# TDC_VTUNE_DAC.net
KiCad netlist of a schematic drawn in Altium Designer
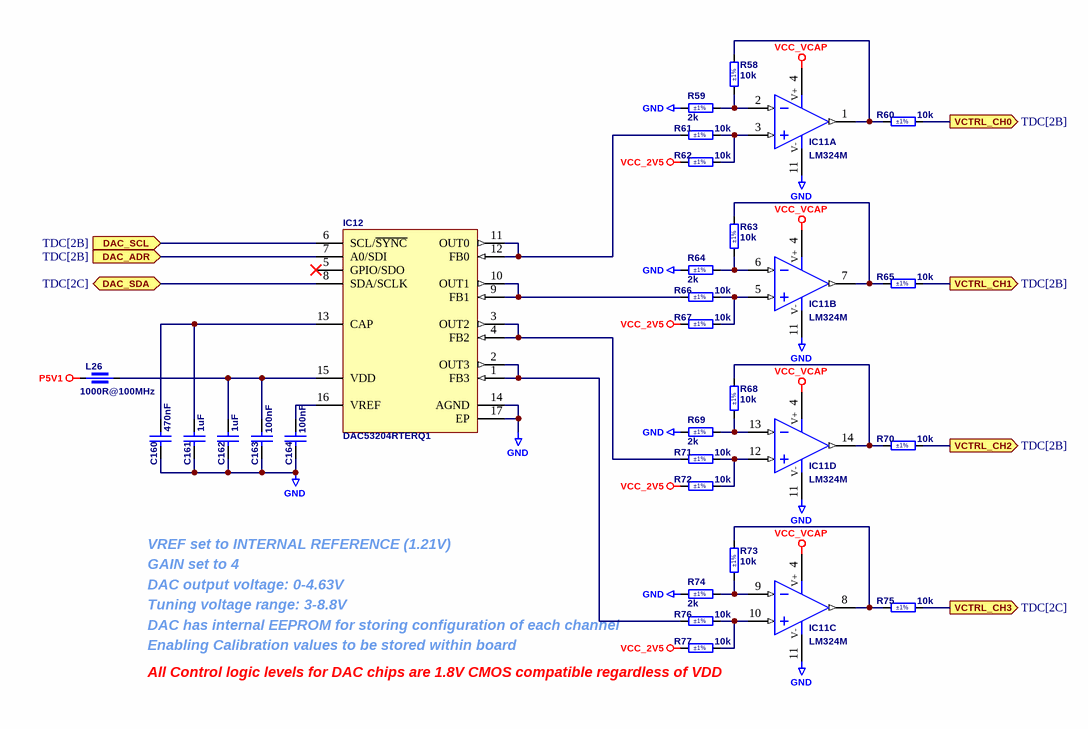
[diagram p0: TDC_VTUNE_DAC.SchDoc]

(export (version "E")
  (design (tool "Eeschema 10.0.6"))
  (components
    (comp (ref "C160")
      (value "470nF")
      (footprint "CAPC1005X55N")
      (description "Non-polarised capacitor")
      (fields
        (field (name "PART NUMBER") "CC0402_470NF_10V_10%_X7R")
        (field (name "VOLTAGE") "10V")
        (field (name "AUTHOR") "CERN DEM BC")
      )
      (libsource (lib "Capacitors") (part "Capacitor - non polarized"))
    )
    (comp (ref "C161")
      (value "1uF")
      (footprint "CAPC1005X55N")
      (description "Non-polarised capacitor")
      (fields
        (field (name "PART NUMBER") "CC0402_1UF_16V_10%_X5R")
        (field (name "VOLTAGE") "16V")
        (field (name "AUTHOR") "CERN DEM JLC")
      )
      (libsource (lib "Capacitors") (part "Capacitor - non polarized"))
    )
    (comp (ref "C162")
      (value "1uF")
      (footprint "CAPC1005X55N")
      (description "Non-polarised capacitor")
      (fields
        (field (name "PART NUMBER") "CC0402_1UF_16V_10%_X5R")
        (field (name "VOLTAGE") "16V")
        (field (name "AUTHOR") "CERN DEM JLC")
      )
      (libsource (lib "Capacitors") (part "Capacitor - non polarized"))
    )
    (comp (ref "C163")
      (value "100nF")
      (footprint "CAPC1005X55N")
      (description "Non-polarised capacitor")
      (fields
        (field (name "PART NUMBER") "CC0402_100NF_16V_10%_X5R")
        (field (name "VOLTAGE") "16V")
        (field (name "AUTHOR") "CERN DEM JLC")
      )
      (libsource (lib "Capacitors") (part "Capacitor - non polarized"))
    )
    (comp (ref "C164")
      (value "100nF")
      (footprint "CAPC1005X55N")
      (description "Non-polarised capacitor")
      (fields
        (field (name "PART NUMBER") "CC0402_100NF_16V_10%_X5R")
        (field (name "VOLTAGE") "16V")
        (field (name "AUTHOR") "CERN DEM JLC")
      )
      (libsource (lib "Capacitors") (part "Capacitor - non polarized"))
    )
    (comp (ref "IC11")
      (value "LM324M")
      (footprint "SOIC127P600X175-14N")
      (description "Quad Operational Amplifier")
      (fields (field (name "MANUFACTURER") "FAIRCHILD SEMICONDUCTOR") (field (name "AUTHOR") "CERN DEM JLC"))
      (libsource (lib "ICs And Semiconductors") (part "Operational Amplifier x4 Type1"))
    )
    (comp (ref "IC12") (value "DAC53204RTERQ1") (libsource (lib "DAC") (part "DAC53204-Q1")))
    (comp (ref "L26")
      (value "1000R@100MHz")
      (footprint "INDC1608X95N")
      (fields
        (field (name "PART NUMBER") "IND0603_MURATA_BLM18KG102SN1")
        (field (name "POWER") "1A")
        (field (name "TOLERANCE") "±25%")
        (field (name "AUTHOR") "CERN DEM HF")
      )
      (libsource (lib "Inductors & Transformers") (part "Ferrite Bead"))
    )
    (comp (ref "R58")
      (value "10k")
      (footprint "RESC1005X40N")
      (description "Resistor - 1%")
      (fields
        (field (name "TOLERANCE") "±1%")
        (field (name "PART NUMBER") "R0402_10K_1%_0.0625W_100PPM")
        (field (name "POWER") "0.0625W")
        (field (name "AUTHOR") "CERN DEM JLC")
      )
      (libsource (lib "Resistors") (part "Resistor - 1%"))
    )
    (comp (ref "R59")
      (value "2k")
      (footprint "RESC1005X40N")
      (description "Resistor - 1%")
      (fields
        (field (name "TOLERANCE") "±1%")
        (field (name "PART NUMBER") "R0402_2K_1%_0.0625W_100PPM")
        (field (name "POWER") "0.0625W")
        (field (name "AUTHOR") "CERN DEM JLC")
      )
      (libsource (lib "Resistors") (part "Resistor - 1%"))
    )
    (comp (ref "R60")
      (value "10k")
      (footprint "RESC1005X40N")
      (description "Resistor - 1%")
      (fields
        (field (name "TOLERANCE") "±1%")
        (field (name "PART NUMBER") "R0402_10K_1%_0.0625W_100PPM")
        (field (name "POWER") "0.0625W")
        (field (name "AUTHOR") "CERN DEM JLC")
      )
      (libsource (lib "Resistors") (part "Resistor - 1%"))
    )
    (comp (ref "R61")
      (value "10k")
      (footprint "RESC1005X40N")
      (description "Resistor - 1%")
      (fields
        (field (name "TOLERANCE") "±1%")
        (field (name "PART NUMBER") "R0402_10K_1%_0.0625W_100PPM")
        (field (name "POWER") "0.0625W")
        (field (name "AUTHOR") "CERN DEM JLC")
      )
      (libsource (lib "Resistors") (part "Resistor - 1%"))
    )
    (comp (ref "R62")
      (value "10k")
      (footprint "RESC1005X40N")
      (description "Resistor - 1%")
      (fields
        (field (name "TOLERANCE") "±1%")
        (field (name "PART NUMBER") "R0402_10K_1%_0.0625W_100PPM")
        (field (name "POWER") "0.0625W")
        (field (name "AUTHOR") "CERN DEM JLC")
      )
      (libsource (lib "Resistors") (part "Resistor - 1%"))
    )
    (comp (ref "R63")
      (value "10k")
      (footprint "RESC1005X40N")
      (description "Resistor - 1%")
      (fields
        (field (name "TOLERANCE") "±1%")
        (field (name "PART NUMBER") "R0402_10K_1%_0.0625W_100PPM")
        (field (name "POWER") "0.0625W")
        (field (name "AUTHOR") "CERN DEM JLC")
      )
      (libsource (lib "Resistors") (part "Resistor - 1%"))
    )
    (comp (ref "R64")
      (value "2k")
      (footprint "RESC1005X40N")
      (description "Resistor - 1%")
      (fields
        (field (name "TOLERANCE") "±1%")
        (field (name "PART NUMBER") "R0402_2K_1%_0.0625W_100PPM")
        (field (name "POWER") "0.0625W")
        (field (name "AUTHOR") "CERN DEM JLC")
      )
      (libsource (lib "Resistors") (part "Resistor - 1%"))
    )
    (comp (ref "R65")
      (value "10k")
      (footprint "RESC1005X40N")
      (description "Resistor - 1%")
      (fields
        (field (name "TOLERANCE") "±1%")
        (field (name "PART NUMBER") "R0402_10K_1%_0.0625W_100PPM")
        (field (name "POWER") "0.0625W")
        (field (name "AUTHOR") "CERN DEM JLC")
      )
      (libsource (lib "Resistors") (part "Resistor - 1%"))
    )
    (comp (ref "R66")
      (value "10k")
      (footprint "RESC1005X40N")
      (description "Resistor - 1%")
      (fields
        (field (name "TOLERANCE") "±1%")
        (field (name "PART NUMBER") "R0402_10K_1%_0.0625W_100PPM")
        (field (name "POWER") "0.0625W")
        (field (name "AUTHOR") "CERN DEM JLC")
      )
      (libsource (lib "Resistors") (part "Resistor - 1%"))
    )
    (comp (ref "R67")
      (value "10k")
      (footprint "RESC1005X40N")
      (description "Resistor - 1%")
      (fields
        (field (name "TOLERANCE") "±1%")
        (field (name "PART NUMBER") "R0402_10K_1%_0.0625W_100PPM")
        (field (name "POWER") "0.0625W")
        (field (name "AUTHOR") "CERN DEM JLC")
      )
      (libsource (lib "Resistors") (part "Resistor - 1%"))
    )
    (comp (ref "R68")
      (value "10k")
      (footprint "RESC1005X40N")
      (description "Resistor - 1%")
      (fields
        (field (name "TOLERANCE") "±1%")
        (field (name "PART NUMBER") "R0402_10K_1%_0.0625W_100PPM")
        (field (name "POWER") "0.0625W")
        (field (name "AUTHOR") "CERN DEM JLC")
      )
      (libsource (lib "Resistors") (part "Resistor - 1%"))
    )
    (comp (ref "R69")
      (value "2k")
      (footprint "RESC1005X40N")
      (description "Resistor - 1%")
      (fields
        (field (name "TOLERANCE") "±1%")
        (field (name "PART NUMBER") "R0402_2K_1%_0.0625W_100PPM")
        (field (name "POWER") "0.0625W")
        (field (name "AUTHOR") "CERN DEM JLC")
      )
      (libsource (lib "Resistors") (part "Resistor - 1%"))
    )
    (comp (ref "R70")
      (value "10k")
      (footprint "RESC1005X40N")
      (description "Resistor - 1%")
      (fields
        (field (name "TOLERANCE") "±1%")
        (field (name "PART NUMBER") "R0402_10K_1%_0.0625W_100PPM")
        (field (name "POWER") "0.0625W")
        (field (name "AUTHOR") "CERN DEM JLC")
      )
      (libsource (lib "Resistors") (part "Resistor - 1%"))
    )
    (comp (ref "R71")
      (value "10k")
      (footprint "RESC1005X40N")
      (description "Resistor - 1%")
      (fields
        (field (name "TOLERANCE") "±1%")
        (field (name "PART NUMBER") "R0402_10K_1%_0.0625W_100PPM")
        (field (name "POWER") "0.0625W")
        (field (name "AUTHOR") "CERN DEM JLC")
      )
      (libsource (lib "Resistors") (part "Resistor - 1%"))
    )
    (comp (ref "R72")
      (value "10k")
      (footprint "RESC1005X40N")
      (description "Resistor - 1%")
      (fields
        (field (name "TOLERANCE") "±1%")
        (field (name "PART NUMBER") "R0402_10K_1%_0.0625W_100PPM")
        (field (name "POWER") "0.0625W")
        (field (name "AUTHOR") "CERN DEM JLC")
      )
      (libsource (lib "Resistors") (part "Resistor - 1%"))
    )
    (comp (ref "R73")
      (value "10k")
      (footprint "RESC1005X40N")
      (description "Resistor - 1%")
      (fields
        (field (name "TOLERANCE") "±1%")
        (field (name "PART NUMBER") "R0402_10K_1%_0.0625W_100PPM")
        (field (name "POWER") "0.0625W")
        (field (name "AUTHOR") "CERN DEM JLC")
      )
      (libsource (lib "Resistors") (part "Resistor - 1%"))
    )
    (comp (ref "R74")
      (value "2k")
      (footprint "RESC1005X40N")
      (description "Resistor - 1%")
      (fields
        (field (name "TOLERANCE") "±1%")
        (field (name "PART NUMBER") "R0402_2K_1%_0.0625W_100PPM")
        (field (name "POWER") "0.0625W")
        (field (name "AUTHOR") "CERN DEM JLC")
      )
      (libsource (lib "Resistors") (part "Resistor - 1%"))
    )
    (comp (ref "R75")
      (value "10k")
      (footprint "RESC1005X40N")
      (description "Resistor - 1%")
      (fields
        (field (name "TOLERANCE") "±1%")
        (field (name "PART NUMBER") "R0402_10K_1%_0.0625W_100PPM")
        (field (name "POWER") "0.0625W")
        (field (name "AUTHOR") "CERN DEM JLC")
      )
      (libsource (lib "Resistors") (part "Resistor - 1%"))
    )
    (comp (ref "R76")
      (value "10k")
      (footprint "RESC1005X40N")
      (description "Resistor - 1%")
      (fields
        (field (name "TOLERANCE") "±1%")
        (field (name "PART NUMBER") "R0402_10K_1%_0.0625W_100PPM")
        (field (name "POWER") "0.0625W")
        (field (name "AUTHOR") "CERN DEM JLC")
      )
      (libsource (lib "Resistors") (part "Resistor - 1%"))
    )
    (comp (ref "R77")
      (value "10k")
      (footprint "RESC1005X40N")
      (description "Resistor - 1%")
      (fields
        (field (name "TOLERANCE") "±1%")
        (field (name "PART NUMBER") "R0402_10K_1%_0.0625W_100PPM")
        (field (name "POWER") "0.0625W")
        (field (name "AUTHOR") "CERN DEM JLC")
      )
      (libsource (lib "Resistors") (part "Resistor - 1%"))
    )
  )
  (nets
    (net (code "1") (name "/DAC_ADR") (class "Default")
      (node (ref "IC12") (pin "7") (pinfunction "A0/SDI_7") (pintype "passive"))
    )
    (net (code "2") (name "/DAC_SCL") (class "Default")
      (node (ref "IC12") (pin "6") (pinfunction "SCL/~{SYNC}_6") (pintype "passive"))
    )
    (net (code "3") (name "/DAC_SDA") (class "Default")
      (node (ref "IC12") (pin "8") (pinfunction "SDA/SCLK_8") (pintype "passive"))
    )
    (net (code "4") (name "/VCTRL_CH0") (class "Default")
      (node (ref "R60") (pin "2") (pinfunction "2_2") (pintype "passive"))
    )
    (net (code "5") (name "/VCTRL_CH1") (class "Default")
      (node (ref "R65") (pin "2") (pinfunction "2_2") (pintype "passive"))
    )
    (net (code "6") (name "/VCTRL_CH2") (class "Default")
      (node (ref "R70") (pin "2") (pinfunction "2_2") (pintype "passive"))
    )
    (net (code "7") (name "/VCTRL_CH3") (class "Default")
      (node (ref "R75") (pin "2") (pinfunction "2_2") (pintype "passive"))
    )
    (net (code "8") (name "GND") (class "Default")
      (node (ref "C160") (pin "1") (pinfunction "1_1") (pintype "passive"))
      (node (ref "C161") (pin "1") (pinfunction "1_1") (pintype "passive"))
      (node (ref "C162") (pin "1") (pinfunction "1_1") (pintype "passive"))
      (node (ref "C163") (pin "1") (pinfunction "1_1") (pintype "passive"))
      (node (ref "C164") (pin "1") (pinfunction "1_1") (pintype "passive"))
      (node (ref "IC11") (pin "11") (pinfunction "V-_11") (pintype "power_in"))
      (node (ref "IC12") (pin "14") (pinfunction "AGND_14") (pintype "power_in"))
      (node (ref "IC12") (pin "17") (pinfunction "EP_17") (pintype "power_in"))
      (node (ref "R59") (pin "1") (pinfunction "1_1") (pintype "passive"))
      (node (ref "R64") (pin "1") (pinfunction "1_1") (pintype "passive"))
      (node (ref "R69") (pin "1") (pinfunction "1_1") (pintype "passive"))
      (node (ref "R74") (pin "1") (pinfunction "1_1") (pintype "passive"))
    )
    (net (code "9") (name "Net-(IC11A-IN+)") (class "Default")
      (node (ref "IC11") (pin "3") (pinfunction "IN+_3") (pintype "input"))
      (node (ref "R61") (pin "2") (pinfunction "2_2") (pintype "passive"))
      (node (ref "R62") (pin "2") (pinfunction "2_2") (pintype "passive"))
    )
    (net (code "10") (name "Net-(IC11A-IN-)") (class "Default")
      (node (ref "IC11") (pin "2") (pinfunction "IN-_2") (pintype "input"))
      (node (ref "R58") (pin "1") (pinfunction "1_1") (pintype "passive"))
      (node (ref "R59") (pin "2") (pinfunction "2_2") (pintype "passive"))
    )
    (net (code "11") (name "Net-(IC11A-OUT)") (class "Default")
      (node (ref "IC11") (pin "1") (pinfunction "OUT_1") (pintype "output"))
      (node (ref "R58") (pin "2") (pinfunction "2_2") (pintype "passive"))
      (node (ref "R60") (pin "1") (pinfunction "1_1") (pintype "passive"))
    )
    (net (code "12") (name "Net-(IC11B-IN+)") (class "Default")
      (node (ref "IC11") (pin "5") (pinfunction "IN+_5") (pintype "input"))
      (node (ref "R66") (pin "2") (pinfunction "2_2") (pintype "passive"))
      (node (ref "R67") (pin "2") (pinfunction "2_2") (pintype "passive"))
    )
    (net (code "13") (name "Net-(IC11B-IN-)") (class "Default")
      (node (ref "IC11") (pin "6") (pinfunction "IN-_6") (pintype "input"))
      (node (ref "R63") (pin "1") (pinfunction "1_1") (pintype "passive"))
      (node (ref "R64") (pin "2") (pinfunction "2_2") (pintype "passive"))
    )
    (net (code "14") (name "Net-(IC11B-OUT)") (class "Default")
      (node (ref "IC11") (pin "7") (pinfunction "OUT_7") (pintype "output"))
      (node (ref "R63") (pin "2") (pinfunction "2_2") (pintype "passive"))
      (node (ref "R65") (pin "1") (pinfunction "1_1") (pintype "passive"))
    )
    (net (code "15") (name "Net-(IC11C-IN+)") (class "Default")
      (node (ref "IC11") (pin "10") (pinfunction "IN+_10") (pintype "input"))
      (node (ref "R76") (pin "2") (pinfunction "2_2") (pintype "passive"))
      (node (ref "R77") (pin "2") (pinfunction "2_2") (pintype "passive"))
    )
    (net (code "16") (name "Net-(IC11C-IN-)") (class "Default")
      (node (ref "IC11") (pin "9") (pinfunction "IN-_9") (pintype "input"))
      (node (ref "R73") (pin "1") (pinfunction "1_1") (pintype "passive"))
      (node (ref "R74") (pin "2") (pinfunction "2_2") (pintype "passive"))
    )
    (net (code "17") (name "Net-(IC11C-OUT)") (class "Default")
      (node (ref "IC11") (pin "8") (pinfunction "OUT_8") (pintype "output"))
      (node (ref "R73") (pin "2") (pinfunction "2_2") (pintype "passive"))
      (node (ref "R75") (pin "1") (pinfunction "1_1") (pintype "passive"))
    )
    (net (code "18") (name "Net-(IC11D-IN+)") (class "Default")
      (node (ref "IC11") (pin "12") (pinfunction "IN+_12") (pintype "input"))
      (node (ref "R71") (pin "2") (pinfunction "2_2") (pintype "passive"))
      (node (ref "R72") (pin "2") (pinfunction "2_2") (pintype "passive"))
    )
    (net (code "19") (name "Net-(IC11D-IN-)") (class "Default")
      (node (ref "IC11") (pin "13") (pinfunction "IN-_13") (pintype "input"))
      (node (ref "R68") (pin "1") (pinfunction "1_1") (pintype "passive"))
      (node (ref "R69") (pin "2") (pinfunction "2_2") (pintype "passive"))
    )
    (net (code "20") (name "Net-(IC11D-OUT)") (class "Default")
      (node (ref "IC11") (pin "14") (pinfunction "OUT_14") (pintype "output"))
      (node (ref "R68") (pin "2") (pinfunction "2_2") (pintype "passive"))
      (node (ref "R70") (pin "1") (pinfunction "1_1") (pintype "passive"))
    )
    (net (code "21") (name "Net-(IC12-CAP)") (class "Default")
      (node (ref "C160") (pin "2") (pinfunction "2_2") (pintype "passive"))
      (node (ref "C161") (pin "2") (pinfunction "2_2") (pintype "passive"))
      (node (ref "IC12") (pin "13") (pinfunction "CAP_13") (pintype "passive"))
    )
    (net (code "22") (name "Net-(IC12-FB0)") (class "Default")
      (node (ref "IC12") (pin "11") (pinfunction "OUT0_11") (pintype "output"))
      (node (ref "IC12") (pin "12") (pinfunction "FB0_12") (pintype "input"))
      (node (ref "R61") (pin "1") (pinfunction "1_1") (pintype "passive"))
    )
    (net (code "23") (name "Net-(IC12-FB1)") (class "Default")
      (node (ref "IC12") (pin "10") (pinfunction "OUT1_10") (pintype "output"))
      (node (ref "IC12") (pin "9") (pinfunction "FB1_9") (pintype "input"))
      (node (ref "R66") (pin "1") (pinfunction "1_1") (pintype "passive"))
    )
    (net (code "24") (name "Net-(IC12-FB2)") (class "Default")
      (node (ref "IC12") (pin "3") (pinfunction "OUT2_3") (pintype "output"))
      (node (ref "IC12") (pin "4") (pinfunction "FB2_4") (pintype "input"))
      (node (ref "R71") (pin "1") (pinfunction "1_1") (pintype "passive"))
    )
    (net (code "25") (name "Net-(IC12-FB3)") (class "Default")
      (node (ref "IC12") (pin "1") (pinfunction "FB3_1") (pintype "input"))
      (node (ref "IC12") (pin "2") (pinfunction "OUT3_2") (pintype "output"))
      (node (ref "R76") (pin "1") (pinfunction "1_1") (pintype "passive"))
    )
    (net (code "26") (name "Net-(IC12-VDD)") (class "Default")
      (node (ref "C162") (pin "2") (pinfunction "2_2") (pintype "passive"))
      (node (ref "C163") (pin "2") (pinfunction "2_2") (pintype "passive"))
      (node (ref "IC12") (pin "15") (pinfunction "VDD_15") (pintype "power_in"))
      (node (ref "L26") (pin "2") (pinfunction "2_2") (pintype "passive"))
    )
    (net (code "27") (name "Net-(IC12-VREF)") (class "Default")
      (node (ref "C164") (pin "2") (pinfunction "2_2") (pintype "passive"))
      (node (ref "IC12") (pin "16") (pinfunction "VREF_16") (pintype "passive"))
    )
    (net (code "28") (name "P5V1") (class "Default")
      (node (ref "L26") (pin "1") (pinfunction "1_1") (pintype "passive"))
    )
    (net (code "29") (name "VCC_2V5") (class "Default")
      (node (ref "R62") (pin "1") (pinfunction "1_1") (pintype "passive"))
      (node (ref "R67") (pin "1") (pinfunction "1_1") (pintype "passive"))
      (node (ref "R72") (pin "1") (pinfunction "1_1") (pintype "passive"))
      (node (ref "R77") (pin "1") (pinfunction "1_1") (pintype "passive"))
    )
    (net (code "30") (name "VCC_VCAP") (class "Default")
      (node (ref "IC11") (pin "4") (pinfunction "V+_4") (pintype "power_in"))
    )
    (net (code "31") (name "unconnected-(IC12-GPIO{slash}SDO-Pad5)") (class "Default")
      (node (ref "IC12") (pin "5") (pinfunction "GPIO/SDO_5") (pintype "passive+no_connect"))
    )
  )
)
